# LithiumChargerShematics.net
KiCad netlist of a schematic drawn in Altium Designer
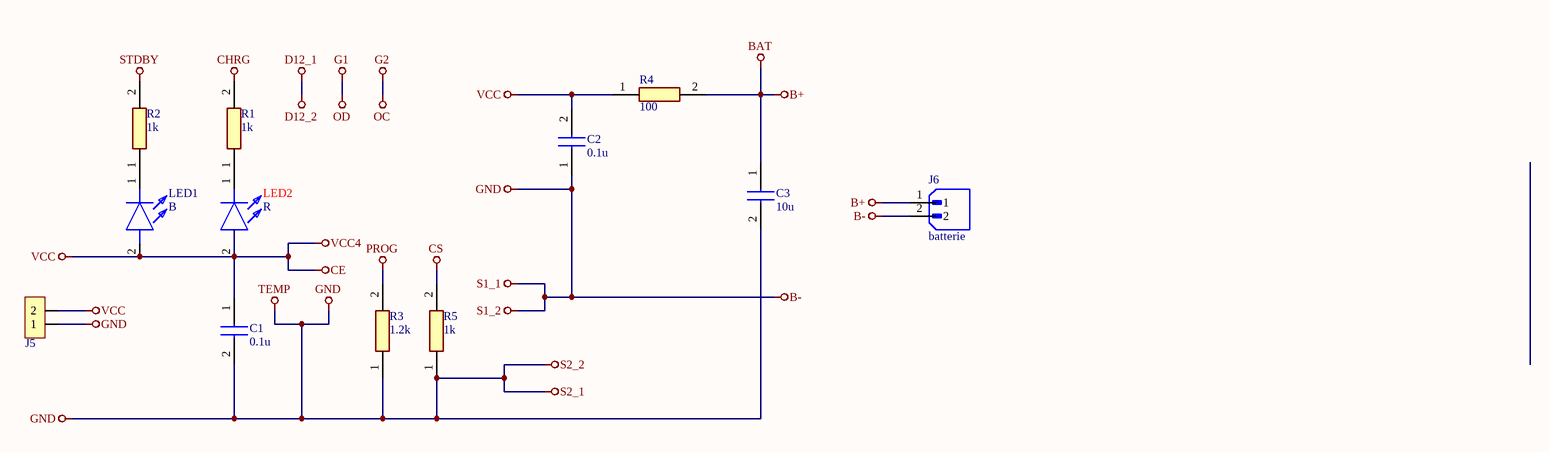
[diagram p0: LithiumChargerShematics.SchDoc]

(export (version "E")
  (design (tool "Eeschema 10.0.6"))
  (components
    (comp (ref "C1")
      (value "0.1u")
      (footprint "SamacSys:CAPC2012X94N")
      (description "Capacitor")
      (fields
        (field (name "MANUFACTURER_PART_NUMBER") "08055A331FAT2A")
        (field (name "MOUSER PART NUMBER") "581-08055A331FAT2A")
      )
      (libsource (lib "SamacSys") (part "08055A331FAT2A"))
    )
    (comp (ref "C2")
      (value "0.1u")
      (footprint "SamacSys:CAPC2013X140N")
      (description "Capacitor")
      (fields
        (field (name "MANUFACTURER_PART_NUMBER") "08053C474JAT2A")
        (field (name "MOUSER PART NUMBER") "581-08053C474JAT2A")
      )
      (libsource (lib "SamacSys") (part "08053C474JAT2A"))
    )
    (comp (ref "C3")
      (value "10u")
      (footprint "SamacSys:CAPC2013X140N")
      (description "Capacitor")
      (fields
        (field (name "MANUFACTURER_PART_NUMBER") "08053C474JAT2A")
        (field (name "MOUSER PART NUMBER") "581-08053C474JAT2A")
      )
      (libsource (lib "SamacSys") (part "08053C474JAT2A"))
    )
    (comp (ref "J5")
      (value "Header Pins")
      (footprint "HEADER PIN 1x2")
      (libsource (lib "ACR Components") (part "Header Pins 1x2"))
    )
    (comp (ref "J6")
      (value "batterie")
      (footprint "JST_B2B-XH-A(LF)(SN)")
      (description "Connector Header Through Hole 2 position 0.098 (2.50mm)")
      (fields (field (name "MF") "JST Sales America Inc.") (field (name "MP") "B2B-XH-A(LF)(SN)"))
      (libsource (lib "B2B-XH-A(LF)(SN)") (part "B2B-XH-A(LF)(SN)"))
    )
    (comp (ref "LED1")
      (value "B")
      (footprint "SamacSys:LEDM2012X80N")
      (description "LED")
      (fields
        (field (name "MANUFACTURER_PART_NUMBER") "150080GS75000")
        (field (name "MOUSER PART NUMBER") "710-150080GS75000")
      )
      (libsource (lib "SamacSys") (part "150080GS75000"))
    )
    (comp (ref "LED2")
      (value "R")
      (footprint "SamacSys:LEDM2012X80N")
      (description "LED")
      (fields
        (field (name "MANUFACTURER_PART_NUMBER") "150080GS75000")
        (field (name "MOUSER PART NUMBER") "710-150080GS75000")
      )
      (libsource (lib "SamacSys") (part "150080GS75000"))
    )
    (comp (ref "R1")
      (value "1k")
      (footprint "SamacSys:RESC2012X65N")
      (description "Resistor")
      (fields (field (name "MANUFACTURER_PART_NUMBER") "CPF0805B102RE1"))
      (libsource (lib "SamacSys") (part "CPF0805B102RE1"))
    )
    (comp (ref "R2")
      (value "1k")
      (footprint "SamacSys:RESC2012X65N")
      (description "Resistor")
      (fields
        (field (name "MANUFACTURER_PART_NUMBER") "CPF0805B10K5E1")
        (field (name "MOUSER PART NUMBER") "279-CPF0805B10K5E1")
      )
      (libsource (lib "SamacSys") (part "CPF0805B10K5E1"))
    )
    (comp (ref "R3")
      (value "1.2k")
      (footprint "SamacSys:RESC2012X65N")
      (description "Resistor")
      (fields (field (name "MANUFACTURER_PART_NUMBER") "CPF0805B102RE1"))
      (libsource (lib "SamacSys") (part "CPF0805B102RE1"))
    )
    (comp (ref "R4")
      (value "100")
      (footprint "SamacSys:RESC2012X65N")
      (description "Resistor")
      (fields (field (name "MANUFACTURER_PART_NUMBER") "CPF0805B102RE1"))
      (libsource (lib "") (part "CPF0805B102RE1_1"))
    )
    (comp (ref "R5")
      (value "1k")
      (footprint "SamacSys:RESC2012X65N")
      (description "Resistor")
      (fields (field (name "MANUFACTURER_PART_NUMBER") "CPF0805B102RE1"))
      (libsource (lib "SamacSys") (part "CPF0805B102RE1"))
    )
  )
  (nets
    (net (code "1") (name "B+") (class "Default")
      (node (ref "C3") (pin "1") (pinfunction "C1_1") (pintype "passive"))
      (node (ref "J6") (pin "1") (pinfunction "1_1") (pintype "passive"))
      (node (ref "R4") (pin "2") (pinfunction "2_2") (pintype "passive"))
    )
    (net (code "2") (name "B-") (class "Default")
      (node (ref "C1") (pin "2") (pinfunction "2_2") (pintype "passive"))
      (node (ref "C2") (pin "1") (pinfunction "C1_1") (pintype "passive"))
      (node (ref "C3") (pin "2") (pinfunction "C2_2") (pintype "passive"))
      (node (ref "J5") (pin "1") (pinfunction "1_1") (pintype "passive"))
      (node (ref "J6") (pin "2") (pinfunction "2_2") (pintype "passive"))
      (node (ref "R3") (pin "1") (pinfunction "1_1") (pintype "passive"))
      (node (ref "R5") (pin "1") (pinfunction "1_1") (pintype "passive"))
    )
    (net (code "3") (name "CE") (class "Default")
      (node (ref "C1") (pin "1") (pinfunction "1_1") (pintype "passive"))
      (node (ref "C2") (pin "2") (pinfunction "C2_2") (pintype "passive"))
      (node (ref "J5") (pin "2") (pinfunction "2_2") (pintype "passive"))
      (node (ref "LED1") (pin "2") (pinfunction "A_2") (pintype "passive"))
      (node (ref "LED2") (pin "2") (pinfunction "A_2") (pintype "passive"))
      (node (ref "R4") (pin "1") (pinfunction "1_1") (pintype "passive"))
    )
    (net (code "4") (name "CHRG") (class "Default")
      (node (ref "R1") (pin "2") (pinfunction "2_2") (pintype "passive"))
    )
    (net (code "5") (name "CS") (class "Default")
      (node (ref "R5") (pin "2") (pinfunction "2_2") (pintype "passive"))
    )
    (net (code "9") (name "Net-(LED1-K)") (class "Default")
      (node (ref "LED1") (pin "1") (pinfunction "K_1") (pintype "passive"))
      (node (ref "R2") (pin "1") (pinfunction "1_1") (pintype "passive"))
    )
    (net (code "10") (name "Net-(LED2-K)") (class "Default")
      (node (ref "LED2") (pin "1") (pinfunction "K_1") (pintype "passive"))
      (node (ref "R1") (pin "1") (pinfunction "1_1") (pintype "passive"))
    )
    (net (code "11") (name "PROG") (class "Default")
      (node (ref "R3") (pin "2") (pinfunction "2_2") (pintype "passive"))
    )
    (net (code "12") (name "STDBY") (class "Default")
      (node (ref "R2") (pin "2") (pinfunction "2_2") (pintype "passive"))
    )
  )
)
